# W005X.net
KiCad netlist of a schematic drawn in EAGLE
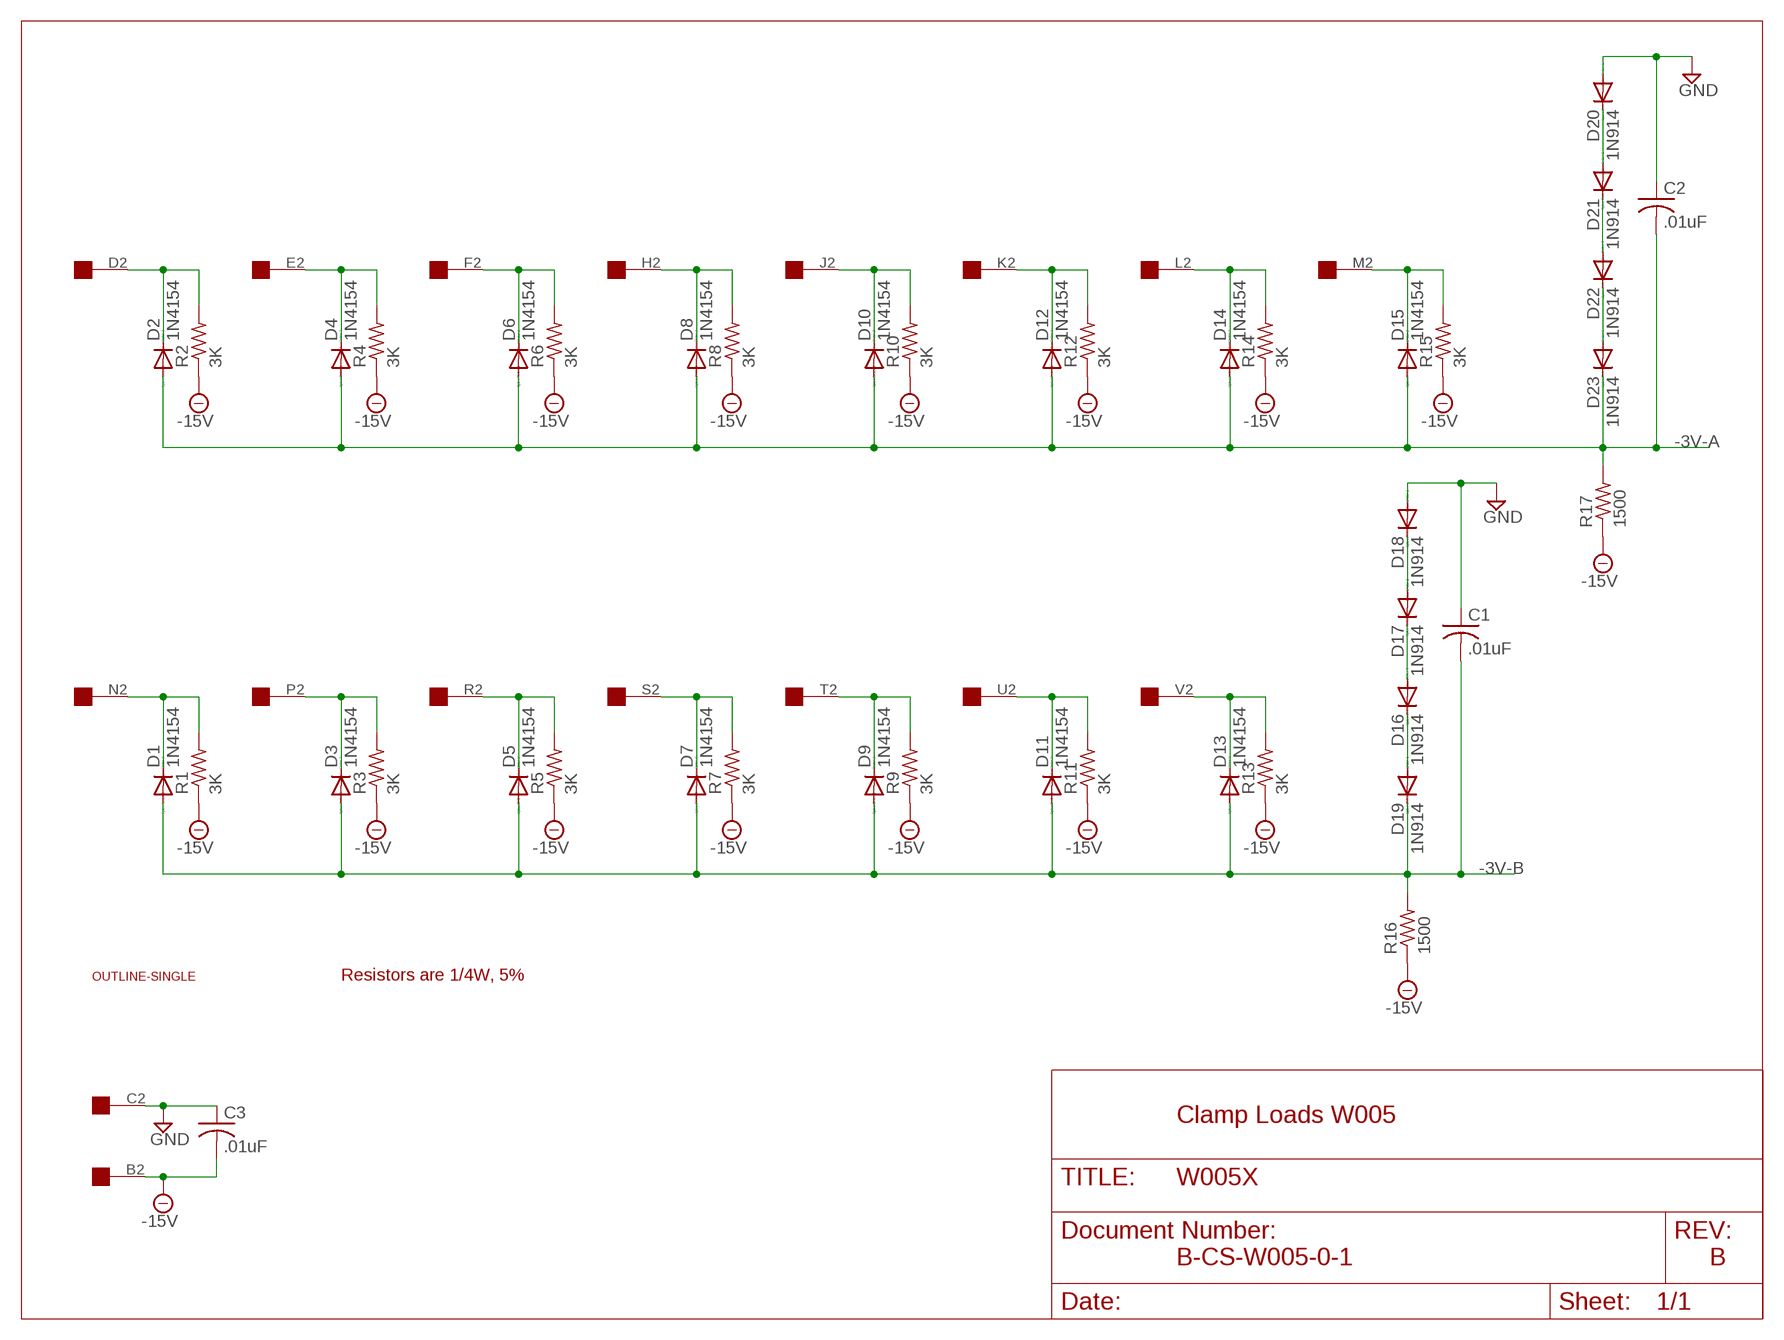
[diagram p0: schematic, sheet 1]

(export (version "E")
  (design (tool "Eeschema 10.0.6"))
  (components
    (comp (ref "C1")
      (value ".01uF")
      (footprint "eagle-import:C050-025X075")
      (libsource (lib "eagle-import") (part "C-US050-025X075"))
    )
    (comp (ref "C2")
      (value ".01uF")
      (footprint "eagle-import:C050-025X075")
      (libsource (lib "eagle-import") (part "C-US050-025X075"))
    )
    (comp (ref "C3")
      (value ".01uF")
      (footprint "eagle-import:C050-025X075")
      (libsource (lib "eagle-import") (part "C-US050-025X075"))
    )
    (comp (ref "D1")
      (value "1N4154")
      (footprint "eagle-import:DO35-10")
      (libsource (lib "eagle-import") (part "1N4148DO35-10"))
    )
    (comp (ref "D2")
      (value "1N4154")
      (footprint "eagle-import:DO35-10")
      (libsource (lib "eagle-import") (part "1N4148DO35-10"))
    )
    (comp (ref "D3")
      (value "1N4154")
      (footprint "eagle-import:DO35-10")
      (libsource (lib "eagle-import") (part "1N4148DO35-10"))
    )
    (comp (ref "D4")
      (value "1N4154")
      (footprint "eagle-import:DO35-10")
      (libsource (lib "eagle-import") (part "1N4148DO35-10"))
    )
    (comp (ref "D5")
      (value "1N4154")
      (footprint "eagle-import:DO35-10")
      (libsource (lib "eagle-import") (part "1N4148DO35-10"))
    )
    (comp (ref "D6")
      (value "1N4154")
      (footprint "eagle-import:DO35-10")
      (libsource (lib "eagle-import") (part "1N4148DO35-10"))
    )
    (comp (ref "D7")
      (value "1N4154")
      (footprint "eagle-import:DO35-10")
      (libsource (lib "eagle-import") (part "1N4148DO35-10"))
    )
    (comp (ref "D8")
      (value "1N4154")
      (footprint "eagle-import:DO35-10")
      (libsource (lib "eagle-import") (part "1N4148DO35-10"))
    )
    (comp (ref "D9")
      (value "1N4154")
      (footprint "eagle-import:DO35-10")
      (libsource (lib "eagle-import") (part "1N4148DO35-10"))
    )
    (comp (ref "D10")
      (value "1N4154")
      (footprint "eagle-import:DO35-10")
      (libsource (lib "eagle-import") (part "1N4148DO35-10"))
    )
    (comp (ref "D11")
      (value "1N4154")
      (footprint "eagle-import:DO35-10")
      (libsource (lib "eagle-import") (part "1N4148DO35-10"))
    )
    (comp (ref "D12")
      (value "1N4154")
      (footprint "eagle-import:DO35-10")
      (libsource (lib "eagle-import") (part "1N4148DO35-10"))
    )
    (comp (ref "D13")
      (value "1N4154")
      (footprint "eagle-import:DO35-10")
      (libsource (lib "eagle-import") (part "1N4148DO35-10"))
    )
    (comp (ref "D14")
      (value "1N4154")
      (footprint "eagle-import:DO35-10")
      (libsource (lib "eagle-import") (part "1N4148DO35-10"))
    )
    (comp (ref "D15")
      (value "1N4154")
      (footprint "eagle-import:DO35-10")
      (libsource (lib "eagle-import") (part "1N4148DO35-10"))
    )
    (comp (ref "D16")
      (value "1N914")
      (footprint "eagle-import:DO35-10")
      (libsource (lib "eagle-import") (part "1N4148DO35-10"))
    )
    (comp (ref "D17")
      (value "1N914")
      (footprint "eagle-import:DO35-10")
      (libsource (lib "eagle-import") (part "1N4148DO35-10"))
    )
    (comp (ref "D18")
      (value "1N914")
      (footprint "eagle-import:DO35-10")
      (libsource (lib "eagle-import") (part "1N4148DO35-10"))
    )
    (comp (ref "D19")
      (value "1N914")
      (footprint "eagle-import:DO35-10")
      (libsource (lib "eagle-import") (part "1N4148DO35-10"))
    )
    (comp (ref "D20")
      (value "1N914")
      (footprint "eagle-import:DO35-10")
      (libsource (lib "eagle-import") (part "1N4148DO35-10"))
    )
    (comp (ref "D21")
      (value "1N914")
      (footprint "eagle-import:DO35-10")
      (libsource (lib "eagle-import") (part "1N4148DO35-10"))
    )
    (comp (ref "D22")
      (value "1N914")
      (footprint "eagle-import:DO35-10")
      (libsource (lib "eagle-import") (part "1N4148DO35-10"))
    )
    (comp (ref "D23")
      (value "1N914")
      (footprint "eagle-import:DO35-10")
      (libsource (lib "eagle-import") (part "1N4148DO35-10"))
    )
    (comp (ref "R1")
      (value "3K")
      (footprint "eagle-import:0207_10")
      (libsource (lib "eagle-import") (part "R-US_0207/10"))
    )
    (comp (ref "R2")
      (value "3K")
      (footprint "eagle-import:0207_10")
      (libsource (lib "eagle-import") (part "R-US_0207/10"))
    )
    (comp (ref "R3")
      (value "3K")
      (footprint "eagle-import:0207_10")
      (libsource (lib "eagle-import") (part "R-US_0207/10"))
    )
    (comp (ref "R4")
      (value "3K")
      (footprint "eagle-import:0207_10")
      (libsource (lib "eagle-import") (part "R-US_0207/10"))
    )
    (comp (ref "R5")
      (value "3K")
      (footprint "eagle-import:0207_10")
      (libsource (lib "eagle-import") (part "R-US_0207/10"))
    )
    (comp (ref "R6")
      (value "3K")
      (footprint "eagle-import:0207_10")
      (libsource (lib "eagle-import") (part "R-US_0207/10"))
    )
    (comp (ref "R7")
      (value "3K")
      (footprint "eagle-import:0207_10")
      (libsource (lib "eagle-import") (part "R-US_0207/10"))
    )
    (comp (ref "R8")
      (value "3K")
      (footprint "eagle-import:0207_10")
      (libsource (lib "eagle-import") (part "R-US_0207/10"))
    )
    (comp (ref "R9")
      (value "3K")
      (footprint "eagle-import:0207_10")
      (libsource (lib "eagle-import") (part "R-US_0207/10"))
    )
    (comp (ref "R10")
      (value "3K")
      (footprint "eagle-import:0207_10")
      (libsource (lib "eagle-import") (part "R-US_0207/10"))
    )
    (comp (ref "R11")
      (value "3K")
      (footprint "eagle-import:0207_10")
      (libsource (lib "eagle-import") (part "R-US_0207/10"))
    )
    (comp (ref "R12")
      (value "3K")
      (footprint "eagle-import:0207_10")
      (libsource (lib "eagle-import") (part "R-US_0207/10"))
    )
    (comp (ref "R13")
      (value "3K")
      (footprint "eagle-import:0207_10")
      (libsource (lib "eagle-import") (part "R-US_0207/10"))
    )
    (comp (ref "R14")
      (value "3K")
      (footprint "eagle-import:0207_10")
      (libsource (lib "eagle-import") (part "R-US_0207/10"))
    )
    (comp (ref "R15")
      (value "3K")
      (footprint "eagle-import:0207_10")
      (libsource (lib "eagle-import") (part "R-US_0207/10"))
    )
    (comp (ref "R16")
      (value "1500")
      (footprint "eagle-import:0207_10")
      (libsource (lib "eagle-import") (part "R-US_0207/10"))
    )
    (comp (ref "R17")
      (value "1500")
      (footprint "eagle-import:0207_10")
      (libsource (lib "eagle-import") (part "R-US_0207/10"))
    )
    (comp (ref "U$1")
      (value "OUTLINE-SINGLE")
      (footprint "eagle-import:SINGLE")
      (libsource (lib "eagle-import") (part "OUTLINE-SINGLE"))
    )
    (comp (ref "U$2")
      (value "EDGE-1")
      (footprint "eagle-import:EDGE-CON1")
      (libsource (lib "eagle-import") (part "EDGE-1"))
    )
  )
  (nets
    (net (code "1") (name "-15V") (class "Default")
      (node (ref "C3") (pin "2") (pinfunction "2_2") (pintype "passive"))
      (node (ref "R1") (pin "1") (pinfunction "1_1") (pintype "passive"))
      (node (ref "R10") (pin "1") (pinfunction "1_1") (pintype "passive"))
      (node (ref "R11") (pin "1") (pinfunction "1_1") (pintype "passive"))
      (node (ref "R12") (pin "1") (pinfunction "1_1") (pintype "passive"))
      (node (ref "R13") (pin "1") (pinfunction "1_1") (pintype "passive"))
      (node (ref "R14") (pin "1") (pinfunction "1_1") (pintype "passive"))
      (node (ref "R15") (pin "1") (pinfunction "1_1") (pintype "passive"))
      (node (ref "R16") (pin "1") (pinfunction "1_1") (pintype "passive"))
      (node (ref "R17") (pin "1") (pinfunction "1_1") (pintype "passive"))
      (node (ref "R2") (pin "1") (pinfunction "1_1") (pintype "passive"))
      (node (ref "R3") (pin "1") (pinfunction "1_1") (pintype "passive"))
      (node (ref "R4") (pin "1") (pinfunction "1_1") (pintype "passive"))
      (node (ref "R5") (pin "1") (pinfunction "1_1") (pintype "passive"))
      (node (ref "R6") (pin "1") (pinfunction "1_1") (pintype "passive"))
      (node (ref "R7") (pin "1") (pinfunction "1_1") (pintype "passive"))
      (node (ref "R8") (pin "1") (pinfunction "1_1") (pintype "passive"))
      (node (ref "R9") (pin "1") (pinfunction "1_1") (pintype "passive"))
      (node (ref "U$2") (pin "B2") (pinfunction "1_B2") (pintype "bidirectional"))
    )
    (net (code "2") (name "/-3V-A") (class "Default")
      (node (ref "C2") (pin "2") (pinfunction "2_2") (pintype "passive"))
      (node (ref "D10") (pin "A") (pinfunction "A_A") (pintype "passive"))
      (node (ref "D12") (pin "A") (pinfunction "A_A") (pintype "passive"))
      (node (ref "D14") (pin "A") (pinfunction "A_A") (pintype "passive"))
      (node (ref "D15") (pin "A") (pinfunction "A_A") (pintype "passive"))
      (node (ref "D2") (pin "A") (pinfunction "A_A") (pintype "passive"))
      (node (ref "D23") (pin "C") (pinfunction "C_C") (pintype "passive"))
      (node (ref "D4") (pin "A") (pinfunction "A_A") (pintype "passive"))
      (node (ref "D6") (pin "A") (pinfunction "A_A") (pintype "passive"))
      (node (ref "D8") (pin "A") (pinfunction "A_A") (pintype "passive"))
      (node (ref "R17") (pin "2") (pinfunction "2_2") (pintype "passive"))
    )
    (net (code "3") (name "/-3V-B") (class "Default")
      (node (ref "C1") (pin "2") (pinfunction "2_2") (pintype "passive"))
      (node (ref "D1") (pin "A") (pinfunction "A_A") (pintype "passive"))
      (node (ref "D11") (pin "A") (pinfunction "A_A") (pintype "passive"))
      (node (ref "D13") (pin "A") (pinfunction "A_A") (pintype "passive"))
      (node (ref "D19") (pin "C") (pinfunction "C_C") (pintype "passive"))
      (node (ref "D3") (pin "A") (pinfunction "A_A") (pintype "passive"))
      (node (ref "D5") (pin "A") (pinfunction "A_A") (pintype "passive"))
      (node (ref "D7") (pin "A") (pinfunction "A_A") (pintype "passive"))
      (node (ref "D9") (pin "A") (pinfunction "A_A") (pintype "passive"))
      (node (ref "R16") (pin "2") (pinfunction "2_2") (pintype "passive"))
    )
    (net (code "4") (name "GND") (class "Default")
      (node (ref "C1") (pin "1") (pinfunction "1_1") (pintype "passive"))
      (node (ref "C2") (pin "1") (pinfunction "1_1") (pintype "passive"))
      (node (ref "C3") (pin "1") (pinfunction "1_1") (pintype "passive"))
      (node (ref "D18") (pin "A") (pinfunction "A_A") (pintype "passive"))
      (node (ref "D20") (pin "A") (pinfunction "A_A") (pintype "passive"))
      (node (ref "U$2") (pin "C2") (pinfunction "1_C2") (pintype "bidirectional"))
    )
    (net (code "5") (name "Net-(D16-PadA)") (class "Default")
      (node (ref "D16") (pin "A") (pinfunction "A_A") (pintype "passive"))
      (node (ref "D17") (pin "C") (pinfunction "C_C") (pintype "passive"))
    )
    (net (code "6") (name "Net-(D16-PadC)") (class "Default")
      (node (ref "D16") (pin "C") (pinfunction "C_C") (pintype "passive"))
      (node (ref "D19") (pin "A") (pinfunction "A_A") (pintype "passive"))
    )
    (net (code "7") (name "Net-(D17-PadA)") (class "Default")
      (node (ref "D17") (pin "A") (pinfunction "A_A") (pintype "passive"))
      (node (ref "D18") (pin "C") (pinfunction "C_C") (pintype "passive"))
    )
    (net (code "8") (name "Net-(D20-PadC)") (class "Default")
      (node (ref "D20") (pin "C") (pinfunction "C_C") (pintype "passive"))
      (node (ref "D21") (pin "A") (pinfunction "A_A") (pintype "passive"))
    )
    (net (code "9") (name "Net-(D21-PadC)") (class "Default")
      (node (ref "D21") (pin "C") (pinfunction "C_C") (pintype "passive"))
      (node (ref "D22") (pin "A") (pinfunction "A_A") (pintype "passive"))
    )
    (net (code "10") (name "Net-(D22-PadC)") (class "Default")
      (node (ref "D22") (pin "C") (pinfunction "C_C") (pintype "passive"))
      (node (ref "D23") (pin "A") (pinfunction "A_A") (pintype "passive"))
    )
    (net (code "11") (name "Net-(U$2D-1)") (class "Default")
      (node (ref "D2") (pin "C") (pinfunction "C_C") (pintype "passive"))
      (node (ref "R2") (pin "2") (pinfunction "2_2") (pintype "passive"))
      (node (ref "U$2") (pin "D2") (pinfunction "1_D2") (pintype "bidirectional"))
    )
    (net (code "12") (name "Net-(U$2E-1)") (class "Default")
      (node (ref "D4") (pin "C") (pinfunction "C_C") (pintype "passive"))
      (node (ref "R4") (pin "2") (pinfunction "2_2") (pintype "passive"))
      (node (ref "U$2") (pin "E2") (pinfunction "1_E2") (pintype "bidirectional"))
    )
    (net (code "13") (name "Net-(U$2F-1)") (class "Default")
      (node (ref "D6") (pin "C") (pinfunction "C_C") (pintype "passive"))
      (node (ref "R6") (pin "2") (pinfunction "2_2") (pintype "passive"))
      (node (ref "U$2") (pin "F2") (pinfunction "1_F2") (pintype "bidirectional"))
    )
    (net (code "14") (name "Net-(U$2G-1)") (class "Default")
      (node (ref "D8") (pin "C") (pinfunction "C_C") (pintype "passive"))
      (node (ref "R8") (pin "2") (pinfunction "2_2") (pintype "passive"))
      (node (ref "U$2") (pin "H2") (pinfunction "1_H2") (pintype "bidirectional"))
    )
    (net (code "15") (name "Net-(U$2H-1)") (class "Default")
      (node (ref "D10") (pin "C") (pinfunction "C_C") (pintype "passive"))
      (node (ref "R10") (pin "2") (pinfunction "2_2") (pintype "passive"))
      (node (ref "U$2") (pin "J2") (pinfunction "1_J2") (pintype "bidirectional"))
    )
    (net (code "16") (name "Net-(U$2I-1)") (class "Default")
      (node (ref "D12") (pin "C") (pinfunction "C_C") (pintype "passive"))
      (node (ref "R12") (pin "2") (pinfunction "2_2") (pintype "passive"))
      (node (ref "U$2") (pin "K2") (pinfunction "1_K2") (pintype "bidirectional"))
    )
    (net (code "17") (name "Net-(U$2J-1)") (class "Default")
      (node (ref "D14") (pin "C") (pinfunction "C_C") (pintype "passive"))
      (node (ref "R14") (pin "2") (pinfunction "2_2") (pintype "passive"))
      (node (ref "U$2") (pin "L2") (pinfunction "1_L2") (pintype "bidirectional"))
    )
    (net (code "18") (name "Net-(U$2K-1)") (class "Default")
      (node (ref "D15") (pin "C") (pinfunction "C_C") (pintype "passive"))
      (node (ref "R15") (pin "2") (pinfunction "2_2") (pintype "passive"))
      (node (ref "U$2") (pin "M2") (pinfunction "1_M2") (pintype "bidirectional"))
    )
    (net (code "19") (name "Net-(U$2L-1)") (class "Default")
      (node (ref "D1") (pin "C") (pinfunction "C_C") (pintype "passive"))
      (node (ref "R1") (pin "2") (pinfunction "2_2") (pintype "passive"))
      (node (ref "U$2") (pin "N2") (pinfunction "1_N2") (pintype "bidirectional"))
    )
    (net (code "20") (name "Net-(U$2M-1)") (class "Default")
      (node (ref "D3") (pin "C") (pinfunction "C_C") (pintype "passive"))
      (node (ref "R3") (pin "2") (pinfunction "2_2") (pintype "passive"))
      (node (ref "U$2") (pin "P2") (pinfunction "1_P2") (pintype "bidirectional"))
    )
    (net (code "21") (name "Net-(U$2N-1)") (class "Default")
      (node (ref "D5") (pin "C") (pinfunction "C_C") (pintype "passive"))
      (node (ref "R5") (pin "2") (pinfunction "2_2") (pintype "passive"))
      (node (ref "U$2") (pin "R2") (pinfunction "1_R2") (pintype "bidirectional"))
    )
    (net (code "22") (name "Net-(U$2O-1)") (class "Default")
      (node (ref "D7") (pin "C") (pinfunction "C_C") (pintype "passive"))
      (node (ref "R7") (pin "2") (pinfunction "2_2") (pintype "passive"))
      (node (ref "U$2") (pin "S2") (pinfunction "1_S2") (pintype "bidirectional"))
    )
    (net (code "23") (name "Net-(U$2P-1)") (class "Default")
      (node (ref "D9") (pin "C") (pinfunction "C_C") (pintype "passive"))
      (node (ref "R9") (pin "2") (pinfunction "2_2") (pintype "passive"))
      (node (ref "U$2") (pin "T2") (pinfunction "1_T2") (pintype "bidirectional"))
    )
    (net (code "24") (name "Net-(U$2Q-1)") (class "Default")
      (node (ref "D11") (pin "C") (pinfunction "C_C") (pintype "passive"))
      (node (ref "R11") (pin "2") (pinfunction "2_2") (pintype "passive"))
      (node (ref "U$2") (pin "U2") (pinfunction "1_U2") (pintype "bidirectional"))
    )
    (net (code "25") (name "Net-(U$2R-1)") (class "Default")
      (node (ref "D13") (pin "C") (pinfunction "C_C") (pintype "passive"))
      (node (ref "R13") (pin "2") (pinfunction "2_2") (pintype "passive"))
      (node (ref "U$2") (pin "V2") (pinfunction "1_V2") (pintype "bidirectional"))
    )
  )
)
